# PiUnitTest.net
KiCad netlist of a schematic drawn in EAGLE
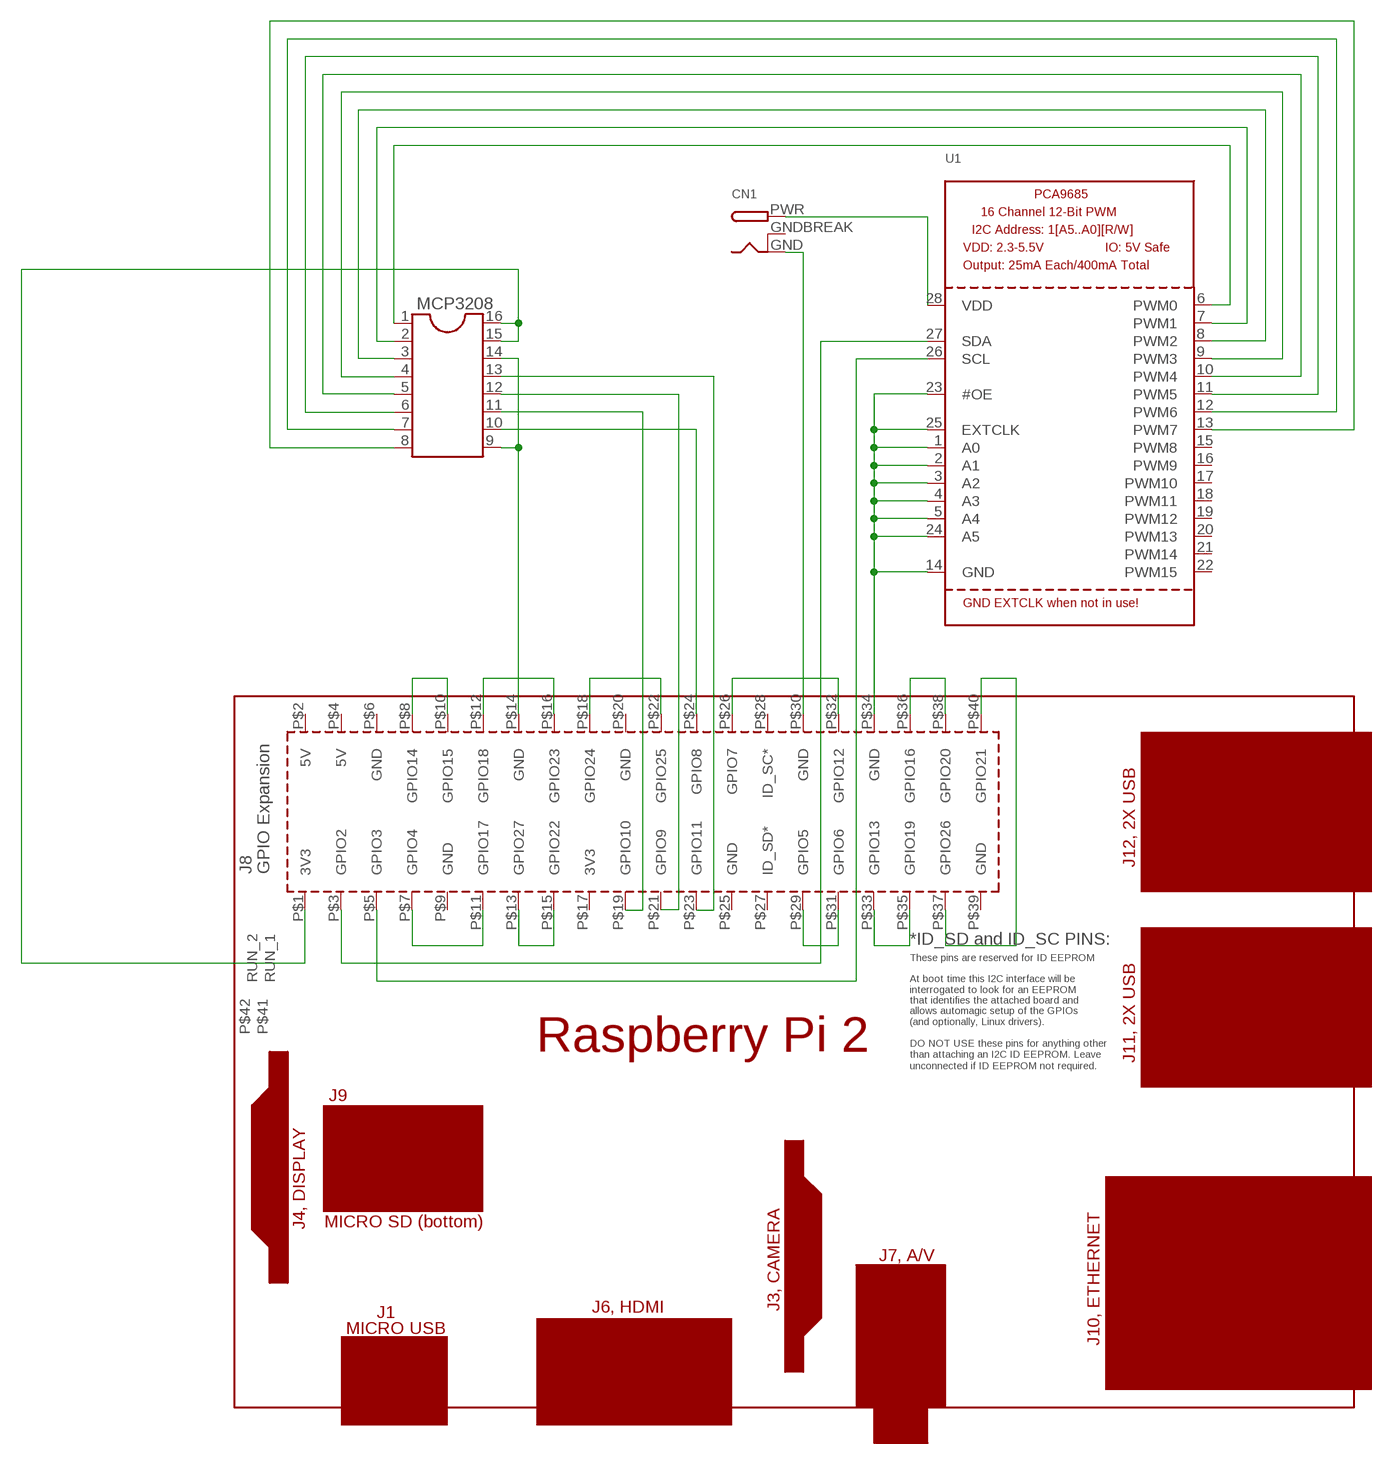
[diagram p0: schematic, sheet 1]

(export (version "E")
  (design (tool "Eeschema 10.0.6"))
  (components
    (comp (ref "CN1")
      (value "DCBARRELPTH")
      (footprint "eagle-import:DCJACK_2MM_PTH")
      (libsource (lib "eagle-import") (part "DCBARRELPTH"))
    )
    (comp (ref "MCP3208")
      (value "DIL16")
      (footprint "eagle-import:DIL16")
      (libsource (lib "eagle-import") (part "DIL16"))
    )
    (comp (ref "PCB1")
      (value "RPI2")
      (footprint "eagle-import:RPI2")
      (libsource (lib "eagle-import") (part "RPI2"))
    )
    (comp (ref "U1")
      (value "PCA9685")
      (footprint "eagle-import:TSSOP28")
      (libsource (lib "eagle-import") (part "PCA9685"))
    )
  )
  (nets
    (net (code "1") (name "/GNDBREAK") (class "Default")
      (node (ref "CN1") (pin "GNDBREAK") (pinfunction "GNDBREAK_GNDBREAK") (pintype "power_in"))
    )
    (net (code "2") (name "Net-(CN1-PadGND)") (class "Default")
      (node (ref "CN1") (pin "GND") (pinfunction "GND_GND") (pintype "power_in"))
      (node (ref "PCB1") (pin "P$30") (pinfunction "GND_P$30") (pintype "bidirectional"))
    )
    (net (code "3") (name "Net-(MCP3208-Pad14)") (class "Default")
      (node (ref "MCP3208") (pin "14") (pinfunction "14_14") (pintype "passive"))
      (node (ref "MCP3208") (pin "9") (pinfunction "9_9") (pintype "passive"))
      (node (ref "PCB1") (pin "P$14") (pinfunction "GND_P$14") (pintype "bidirectional"))
    )
    (net (code "4") (name "Net-(MCP3208-Pad15)") (class "Default")
      (node (ref "MCP3208") (pin "15") (pinfunction "15_15") (pintype "passive"))
      (node (ref "MCP3208") (pin "16") (pinfunction "16_16") (pintype "passive"))
      (node (ref "PCB1") (pin "P$1") (pinfunction "3V3_P$1") (pintype "bidirectional"))
    )
    (net (code "5") (name "Net-(PCB1-GPIO2)") (class "Default")
      (node (ref "PCB1") (pin "P$3") (pinfunction "GPIO2_P$3") (pintype "bidirectional"))
      (node (ref "U1") (pin "27") (pinfunction "SDA_27") (pintype "bidirectional"))
    )
    (net (code "6") (name "Net-(PCB1-GPIO3)") (class "Default")
      (node (ref "PCB1") (pin "P$5") (pinfunction "GPIO3_P$5") (pintype "bidirectional"))
      (node (ref "U1") (pin "26") (pinfunction "SCL_26") (pintype "bidirectional"))
    )
    (net (code "7") (name "Net-(PCB1-GPIO5)") (class "Default")
      (node (ref "PCB1") (pin "P$29") (pinfunction "GPIO5_P$29") (pintype "bidirectional"))
      (node (ref "PCB1") (pin "P$31") (pinfunction "GPIO6_P$31") (pintype "bidirectional"))
    )
    (net (code "8") (name "Net-(PCB1-GPIO8)") (class "Default")
      (node (ref "MCP3208") (pin "10") (pinfunction "10_10") (pintype "passive"))
      (node (ref "PCB1") (pin "P$24") (pinfunction "GPIO8_P$24") (pintype "bidirectional"))
    )
    (net (code "9") (name "Net-(PCB1-GPIO9)") (class "Default")
      (node (ref "MCP3208") (pin "12") (pinfunction "12_12") (pintype "passive"))
      (node (ref "PCB1") (pin "P$21") (pinfunction "GPIO9_P$21") (pintype "bidirectional"))
    )
    (net (code "10") (name "Net-(PCB1-GPIO10)") (class "Default")
      (node (ref "MCP3208") (pin "11") (pinfunction "11_11") (pintype "passive"))
      (node (ref "PCB1") (pin "P$19") (pinfunction "GPIO10_P$19") (pintype "bidirectional"))
    )
    (net (code "11") (name "Net-(PCB1-GPIO11)") (class "Default")
      (node (ref "MCP3208") (pin "13") (pinfunction "13_13") (pintype "passive"))
      (node (ref "PCB1") (pin "P$23") (pinfunction "GPIO11_P$23") (pintype "bidirectional"))
    )
    (net (code "12") (name "Net-(PCB1-GPIO12)") (class "Default")
      (node (ref "PCB1") (pin "P$26") (pinfunction "GPIO7_P$26") (pintype "bidirectional"))
      (node (ref "PCB1") (pin "P$32") (pinfunction "GPIO12_P$32") (pintype "bidirectional"))
    )
    (net (code "13") (name "Net-(PCB1-GPIO13)") (class "Default")
      (node (ref "PCB1") (pin "P$33") (pinfunction "GPIO13_P$33") (pintype "bidirectional"))
      (node (ref "PCB1") (pin "P$35") (pinfunction "GPIO19_P$35") (pintype "bidirectional"))
    )
    (net (code "14") (name "Net-(PCB1-GPIO14)") (class "Default")
      (node (ref "PCB1") (pin "P$10") (pinfunction "GPIO15_P$10") (pintype "bidirectional"))
      (node (ref "PCB1") (pin "P$8") (pinfunction "GPIO14_P$8") (pintype "bidirectional"))
    )
    (net (code "15") (name "Net-(PCB1-GPIO16)") (class "Default")
      (node (ref "PCB1") (pin "P$36") (pinfunction "GPIO16_P$36") (pintype "bidirectional"))
      (node (ref "PCB1") (pin "P$38") (pinfunction "GPIO20_P$38") (pintype "bidirectional"))
    )
    (net (code "16") (name "Net-(PCB1-GPIO17)") (class "Default")
      (node (ref "PCB1") (pin "P$11") (pinfunction "GPIO17_P$11") (pintype "bidirectional"))
      (node (ref "PCB1") (pin "P$7") (pinfunction "GPIO4_P$7") (pintype "bidirectional"))
    )
    (net (code "17") (name "Net-(PCB1-GPIO18)") (class "Default")
      (node (ref "PCB1") (pin "P$12") (pinfunction "GPIO18_P$12") (pintype "bidirectional"))
      (node (ref "PCB1") (pin "P$16") (pinfunction "GPIO23_P$16") (pintype "bidirectional"))
    )
    (net (code "18") (name "Net-(PCB1-GPIO21)") (class "Default")
      (node (ref "PCB1") (pin "P$37") (pinfunction "GPIO26_P$37") (pintype "bidirectional"))
      (node (ref "PCB1") (pin "P$40") (pinfunction "GPIO21_P$40") (pintype "bidirectional"))
    )
    (net (code "19") (name "Net-(PCB1-GPIO22)") (class "Default")
      (node (ref "PCB1") (pin "P$13") (pinfunction "GPIO27_P$13") (pintype "bidirectional"))
      (node (ref "PCB1") (pin "P$15") (pinfunction "GPIO22_P$15") (pintype "bidirectional"))
    )
    (net (code "20") (name "Net-(PCB1-GPIO24)") (class "Default")
      (node (ref "PCB1") (pin "P$18") (pinfunction "GPIO24_P$18") (pintype "bidirectional"))
      (node (ref "PCB1") (pin "P$22") (pinfunction "GPIO25_P$22") (pintype "bidirectional"))
    )
    (net (code "21") (name "Net-(U1-#OE)") (class "Default")
      (node (ref "PCB1") (pin "P$34") (pinfunction "GND_P$34") (pintype "bidirectional"))
      (node (ref "U1") (pin "1") (pinfunction "A0_1") (pintype "bidirectional"))
      (node (ref "U1") (pin "14") (pinfunction "GND_14") (pintype "power_in"))
      (node (ref "U1") (pin "2") (pinfunction "A1_2") (pintype "bidirectional"))
      (node (ref "U1") (pin "23") (pinfunction "#OE_23") (pintype "input"))
      (node (ref "U1") (pin "24") (pinfunction "A5_24") (pintype "bidirectional"))
      (node (ref "U1") (pin "25") (pinfunction "EXTCLK_25") (pintype "input"))
      (node (ref "U1") (pin "3") (pinfunction "A2_3") (pintype "bidirectional"))
      (node (ref "U1") (pin "4") (pinfunction "A3_4") (pintype "bidirectional"))
      (node (ref "U1") (pin "5") (pinfunction "A4_5") (pintype "bidirectional"))
    )
    (net (code "22") (name "Net-(U1-PWM0)") (class "Default")
      (node (ref "MCP3208") (pin "1") (pinfunction "1_1") (pintype "passive"))
      (node (ref "U1") (pin "6") (pinfunction "PWM0_6") (pintype "output"))
    )
    (net (code "23") (name "Net-(U1-PWM1)") (class "Default")
      (node (ref "MCP3208") (pin "2") (pinfunction "2_2") (pintype "passive"))
      (node (ref "U1") (pin "7") (pinfunction "PWM1_7") (pintype "output"))
    )
    (net (code "24") (name "Net-(U1-PWM2)") (class "Default")
      (node (ref "MCP3208") (pin "3") (pinfunction "3_3") (pintype "passive"))
      (node (ref "U1") (pin "8") (pinfunction "PWM2_8") (pintype "output"))
    )
    (net (code "25") (name "Net-(U1-PWM3)") (class "Default")
      (node (ref "MCP3208") (pin "4") (pinfunction "4_4") (pintype "passive"))
      (node (ref "U1") (pin "9") (pinfunction "PWM3_9") (pintype "output"))
    )
    (net (code "26") (name "Net-(U1-PWM4)") (class "Default")
      (node (ref "MCP3208") (pin "5") (pinfunction "5_5") (pintype "passive"))
      (node (ref "U1") (pin "10") (pinfunction "PWM4_10") (pintype "output"))
    )
    (net (code "27") (name "Net-(U1-PWM5)") (class "Default")
      (node (ref "MCP3208") (pin "6") (pinfunction "6_6") (pintype "passive"))
      (node (ref "U1") (pin "11") (pinfunction "PWM5_11") (pintype "output"))
    )
    (net (code "28") (name "Net-(U1-PWM6)") (class "Default")
      (node (ref "MCP3208") (pin "7") (pinfunction "7_7") (pintype "passive"))
      (node (ref "U1") (pin "12") (pinfunction "PWM6_12") (pintype "output"))
    )
    (net (code "29") (name "Net-(U1-PWM7)") (class "Default")
      (node (ref "MCP3208") (pin "8") (pinfunction "8_8") (pintype "passive"))
      (node (ref "U1") (pin "13") (pinfunction "PWM7_13") (pintype "output"))
    )
    (net (code "30") (name "Net-(U1-VDD)") (class "Default")
      (node (ref "CN1") (pin "PWR") (pinfunction "PWR_PWR") (pintype "power_in"))
      (node (ref "U1") (pin "28") (pinfunction "VDD_28") (pintype "power_in"))
    )
    (net (code "31") (name "unconnected-(PCB1-3V3-PadP$17)") (class "Default")
      (node (ref "PCB1") (pin "P$17") (pinfunction "3V3_P$17") (pintype "bidirectional"))
    )
    (net (code "32") (name "unconnected-(PCB1-5V-PadP$2)") (class "Default")
      (node (ref "PCB1") (pin "P$2") (pinfunction "5V_P$2") (pintype "bidirectional"))
    )
    (net (code "33") (name "unconnected-(PCB1-5V-PadP$4)") (class "Default")
      (node (ref "PCB1") (pin "P$4") (pinfunction "5V_P$4") (pintype "bidirectional"))
    )
    (net (code "34") (name "unconnected-(PCB1-GND-PadP$6)") (class "Default")
      (node (ref "PCB1") (pin "P$6") (pinfunction "GND_P$6") (pintype "bidirectional"))
    )
    (net (code "35") (name "unconnected-(PCB1-GND-PadP$9)") (class "Default")
      (node (ref "PCB1") (pin "P$9") (pinfunction "GND_P$9") (pintype "bidirectional"))
    )
    (net (code "36") (name "unconnected-(PCB1-GND-PadP$20)") (class "Default")
      (node (ref "PCB1") (pin "P$20") (pinfunction "GND_P$20") (pintype "bidirectional"))
    )
    (net (code "37") (name "unconnected-(PCB1-GND-PadP$25)") (class "Default")
      (node (ref "PCB1") (pin "P$25") (pinfunction "GND_P$25") (pintype "bidirectional"))
    )
    (net (code "38") (name "unconnected-(PCB1-GND-PadP$39)") (class "Default")
      (node (ref "PCB1") (pin "P$39") (pinfunction "GND_P$39") (pintype "bidirectional"))
    )
    (net (code "39") (name "unconnected-(PCB1-ID_SC*-PadP$28)") (class "Default")
      (node (ref "PCB1") (pin "P$28") (pinfunction "ID_SC*_P$28") (pintype "bidirectional"))
    )
    (net (code "40") (name "unconnected-(PCB1-ID_SD*-PadP$27)") (class "Default")
      (node (ref "PCB1") (pin "P$27") (pinfunction "ID_SD*_P$27") (pintype "bidirectional"))
    )
    (net (code "41") (name "unconnected-(PCB1-RUN_1-PadP$41)") (class "Default")
      (node (ref "PCB1") (pin "P$41") (pinfunction "RUN_1_P$41") (pintype "bidirectional"))
    )
    (net (code "42") (name "unconnected-(PCB1-RUN_2-PadP$42)") (class "Default")
      (node (ref "PCB1") (pin "P$42") (pinfunction "RUN_2_P$42") (pintype "bidirectional"))
    )
    (net (code "43") (name "unconnected-(U1-PWM8-Pad15)") (class "Default")
      (node (ref "U1") (pin "15") (pinfunction "PWM8_15") (pintype "output"))
    )
    (net (code "44") (name "unconnected-(U1-PWM9-Pad16)") (class "Default")
      (node (ref "U1") (pin "16") (pinfunction "PWM9_16") (pintype "output"))
    )
    (net (code "45") (name "unconnected-(U1-PWM10-Pad17)") (class "Default")
      (node (ref "U1") (pin "17") (pinfunction "PWM10_17") (pintype "output"))
    )
    (net (code "46") (name "unconnected-(U1-PWM11-Pad18)") (class "Default")
      (node (ref "U1") (pin "18") (pinfunction "PWM11_18") (pintype "output"))
    )
    (net (code "47") (name "unconnected-(U1-PWM12-Pad19)") (class "Default")
      (node (ref "U1") (pin "19") (pinfunction "PWM12_19") (pintype "output"))
    )
    (net (code "48") (name "unconnected-(U1-PWM13-Pad20)") (class "Default")
      (node (ref "U1") (pin "20") (pinfunction "PWM13_20") (pintype "output"))
    )
    (net (code "49") (name "unconnected-(U1-PWM14-Pad21)") (class "Default")
      (node (ref "U1") (pin "21") (pinfunction "PWM14_21") (pintype "output"))
    )
    (net (code "50") (name "unconnected-(U1-PWM15-Pad22)") (class "Default")
      (node (ref "U1") (pin "22") (pinfunction "PWM15_22") (pintype "output"))
    )
  )
)
